# photon_at7020_2.net
KiCad netlist of a schematic drawn in EAGLE
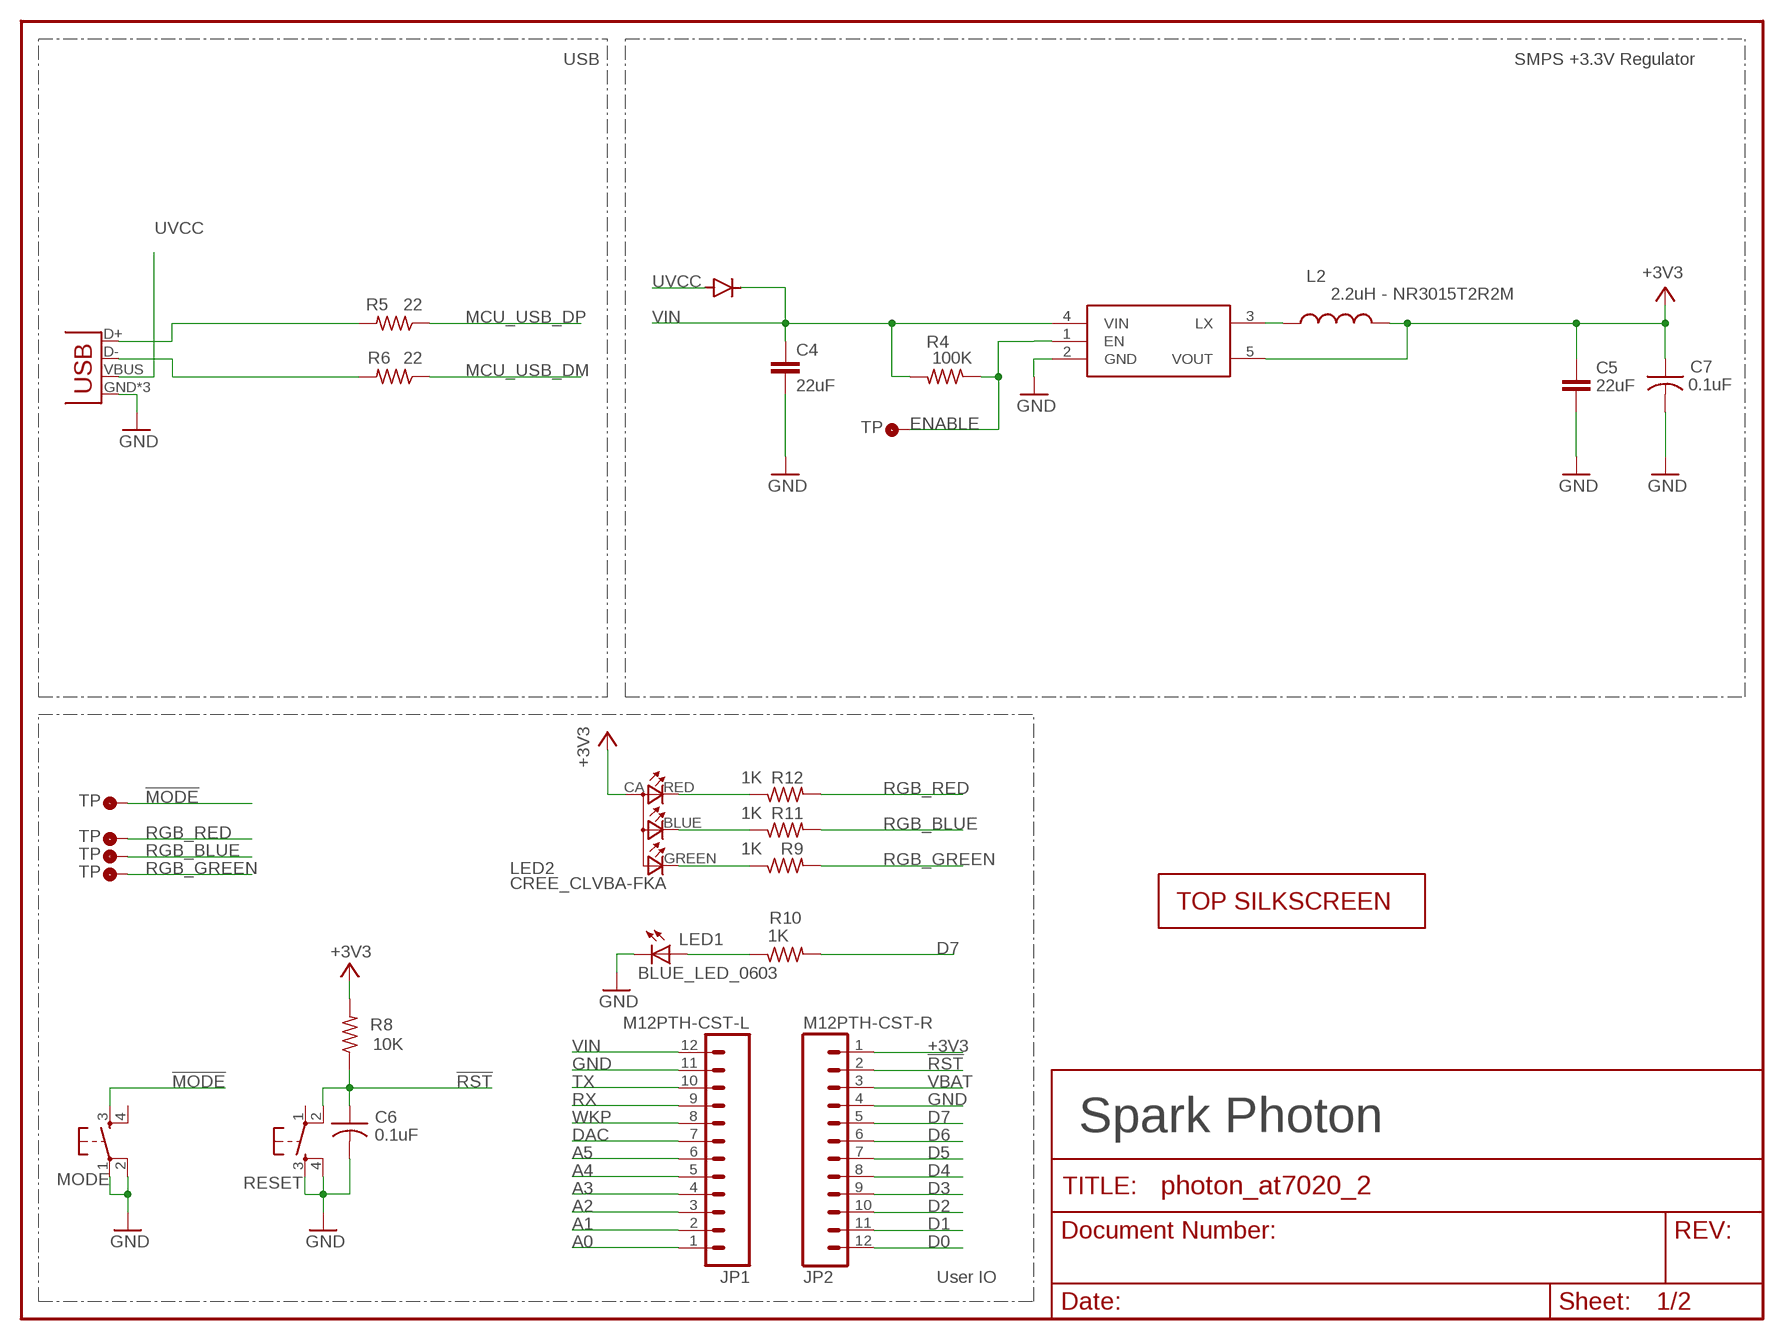
[diagram p0: schematic, sheet 1]
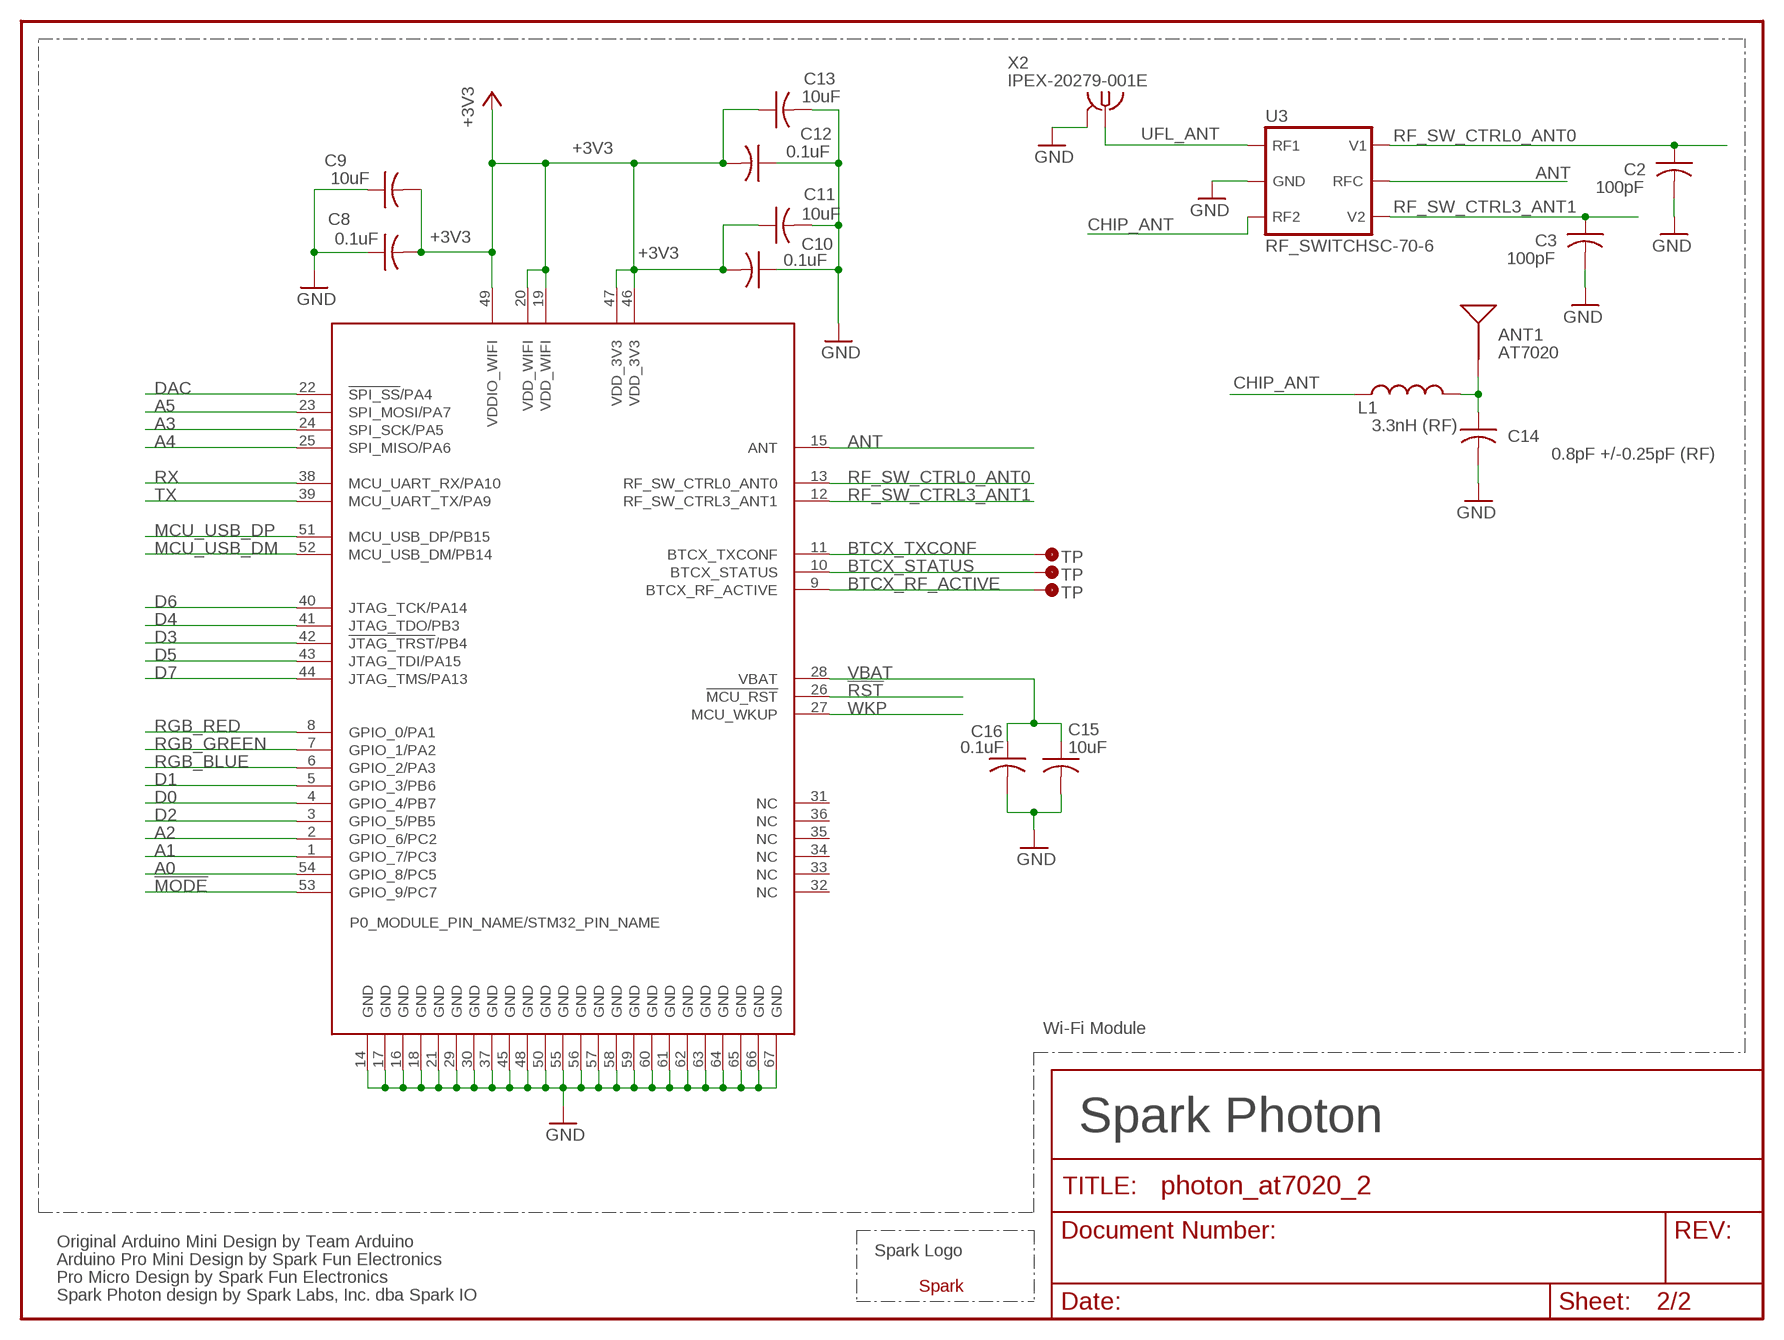
[diagram p1: schematic, sheet 2]

(export (version "E")
  (design (tool "Eeschema 10.0.6"))
  (components
    (comp (ref "ANT1")
      (value "AT7020")
      (footprint "eagle-import:AT7020")
      (libsource (lib "eagle-import") (part "AT7020"))
    )
    (comp (ref "C2")
      (value "100pF")
      (footprint "eagle-import:C0402_B")
      (libsource (lib "eagle-import") (part "C-US"))
    )
    (comp (ref "C3")
      (value "100pF")
      (footprint "eagle-import:C0402_B")
      (libsource (lib "eagle-import") (part "C-US"))
    )
    (comp (ref "C8")
      (value "0.1uF")
      (footprint "eagle-import:C0402_B")
      (libsource (lib "eagle-import") (part "C-US"))
    )
    (comp (ref "C9")
      (value "10uF")
      (footprint "eagle-import:C0402_B")
      (libsource (lib "eagle-import") (part "C-US"))
    )
    (comp (ref "C10")
      (value "0.1uF")
      (footprint "eagle-import:C0402_B")
      (libsource (lib "eagle-import") (part "C-US"))
    )
    (comp (ref "C11")
      (value "10uF")
      (footprint "eagle-import:C0402_B")
      (libsource (lib "eagle-import") (part "C-US"))
    )
    (comp (ref "C12")
      (value "0.1uF")
      (footprint "eagle-import:C0402_B")
      (libsource (lib "eagle-import") (part "C-US"))
    )
    (comp (ref "C13")
      (value "10uF")
      (footprint "eagle-import:C0402_B")
      (libsource (lib "eagle-import") (part "C-US"))
    )
    (comp (ref "C14")
      (value "0.8pF +/-0.25pF (RF)")
      (footprint "eagle-import:C0402_B")
      (libsource (lib "eagle-import") (part "C-US"))
    )
    (comp (ref "C15")
      (value "10uF")
      (footprint "eagle-import:C0402_B")
      (libsource (lib "eagle-import") (part "C-US"))
    )
    (comp (ref "C16")
      (value "0.1uF")
      (footprint "eagle-import:C0402_B")
      (libsource (lib "eagle-import") (part "C-US"))
    )
    (comp (ref "L1")
      (value "3.3nH (RF)")
      (footprint "eagle-import:L0402_B")
      (libsource (lib "eagle-import") (part "INDUCTOR"))
    )
    (comp (ref "U$2")
      (value "SPARK_LOGO2")
      (footprint "eagle-import:SPARK_LOGO2")
      (libsource (lib "eagle-import") (part "SPARK_LOGO2"))
    )
    (comp (ref "U$8")
      (value "TP1")
      (footprint "eagle-import:TP35_BOT")
      (libsource (lib "eagle-import") (part "TP1"))
    )
    (comp (ref "U$9")
      (value "TP1")
      (footprint "eagle-import:TP35_BOT")
      (libsource (lib "eagle-import") (part "TP1"))
    )
    (comp (ref "U$10")
      (value "TP1")
      (footprint "eagle-import:TP35_BOT")
      (libsource (lib "eagle-import") (part "TP1"))
    )
    (comp (ref "U1")
      (value "WM-N-BM-09")
      (footprint "eagle-import:WM-N-BM-09")
      (libsource (lib "eagle-import") (part "WM-N-BM-09"))
    )
    (comp (ref "U3")
      (value "RF_SWITCHSC-70-6")
      (footprint "eagle-import:SC70-6")
      (libsource (lib "eagle-import") (part "RF_SWITCHSC-70-6"))
    )
    (comp (ref "X2")
      (value "IPEX-20279-001E")
      (footprint "eagle-import:IPEX-20279-001E")
      (libsource (lib "eagle-import") (part "IPEX-20279-001E"))
    )
    (comp (ref "BLUE_LED_0603")
      (value "LED0603")
      (footprint "eagle-import:LED-0603")
      (libsource (lib "eagle-import") (part "LED0603"))
    )
    (comp (ref "C4")
      (value "22uF")
      (footprint "eagle-import:C0603")
      (libsource (lib "eagle-import") (part "C-EUC0603"))
    )
    (comp (ref "C5")
      (value "22uF")
      (footprint "eagle-import:C0603")
      (libsource (lib "eagle-import") (part "C-EUC0603"))
    )
    (comp (ref "C6")
      (value "0.1uF")
      (footprint "eagle-import:C0402_B")
      (libsource (lib "eagle-import") (part "C-US"))
    )
    (comp (ref "C7")
      (value "0.1uF")
      (footprint "eagle-import:C0402")
      (libsource (lib "eagle-import") (part "C-USC0402"))
    )
    (comp (ref "D1")
      (value "DIODE")
      (footprint "eagle-import:DIODE-DO-220AA(SMP)")
      (libsource (lib "eagle-import") (part "DIODE"))
    )
    (comp (ref "JP1")
      (value "M12PTH-CST-L")
      (footprint "eagle-import:1X12-CASTELLATED")
      (libsource (lib "eagle-import") (part "M12PTH-CST-L"))
    )
    (comp (ref "JP2")
      (value "M12PTH-CST-R")
      (footprint "eagle-import:1X12-CASTELLATED")
      (libsource (lib "eagle-import") (part "M12PTH-CST-R"))
    )
    (comp (ref "L2")
      (value "2.2uH - NR3015T2R2M")
      (footprint "eagle-import:INDUCTOR-NR3015")
      (libsource (lib "eagle-import") (part "INDUCTORB"))
    )
    (comp (ref "LED2")
      (value "CREE_CLVBA-FKA")
      (footprint "eagle-import:PLCC4-2MM-RGB")
      (libsource (lib "eagle-import") (part "RGB-LED-CLMVB-FKARGB"))
    )
    (comp (ref "MODE")
      (value "KMR211GLFS")
      (footprint "eagle-import:TACTILE_SWITCH_SMD")
      (libsource (lib "eagle-import") (part "TAC_SWITCHSMD"))
    )
    (comp (ref "R4")
      (value "100K")
      (footprint "eagle-import:R0402_B")
      (libsource (lib "eagle-import") (part "R-US_"))
    )
    (comp (ref "R5")
      (value "22")
      (footprint "eagle-import:R0402_B")
      (libsource (lib "eagle-import") (part "R-US_"))
    )
    (comp (ref "R6")
      (value "22")
      (footprint "eagle-import:R0402_B")
      (libsource (lib "eagle-import") (part "R-US_"))
    )
    (comp (ref "R8")
      (value "10K")
      (footprint "eagle-import:R0402_B")
      (libsource (lib "eagle-import") (part "R-US_"))
    )
    (comp (ref "R9")
      (value "1K")
      (footprint "eagle-import:R0402_B")
      (libsource (lib "eagle-import") (part "R-US_"))
    )
    (comp (ref "R10")
      (value "1K")
      (footprint "eagle-import:R0402_B")
      (libsource (lib "eagle-import") (part "R-US_"))
    )
    (comp (ref "R11")
      (value "1K")
      (footprint "eagle-import:R0402_B")
      (libsource (lib "eagle-import") (part "R-US_"))
    )
    (comp (ref "R12")
      (value "1K")
      (footprint "eagle-import:R0402_B")
      (libsource (lib "eagle-import") (part "R-US_"))
    )
    (comp (ref "RESET")
      (value "KMR211GLFS")
      (footprint "eagle-import:TACTILE_SWITCH_SMD")
      (libsource (lib "eagle-import") (part "TAC_SWITCHSMD"))
    )
    (comp (ref "U$1")
      (value "PHOTON-TOP-SS")
      (footprint "eagle-import:PHOTON-TOP-SS")
      (libsource (lib "eagle-import") (part "PHOTON-TOP-SS"))
    )
    (comp (ref "U$3")
      (value "TP1")
      (footprint "eagle-import:TP35_BOT")
      (libsource (lib "eagle-import") (part "TP1"))
    )
    (comp (ref "U$5")
      (value "TP1")
      (footprint "eagle-import:TP35_BOT")
      (libsource (lib "eagle-import") (part "TP1"))
    )
    (comp (ref "U$6")
      (value "TP1")
      (footprint "eagle-import:TP35_BOT")
      (libsource (lib "eagle-import") (part "TP1"))
    )
    (comp (ref "U$7")
      (value "TP1")
      (footprint "eagle-import:TP35_BOT")
      (libsource (lib "eagle-import") (part "TP1"))
    )
    (comp (ref "U$11")
      (value "R8008-33")
      (footprint "eagle-import:SOT23-5")
      (libsource (lib "eagle-import") (part "R8008-33"))
    )
    (comp (ref "U$12")
      (value "TP1")
      (footprint "eagle-import:TP35_BOT")
      (libsource (lib "eagle-import") (part "TP1"))
    )
    (comp (ref "X1")
      (value "USB-MICROB")
      (footprint "eagle-import:USB-MICROB-SLOT-HOLE")
      (libsource (lib "eagle-import") (part "USBUSB-MICROB-SLOT-HOLE"))
    )
  )
  (nets
    (net (code "1") (name "+3V3") (class "Default")
      (node (ref "C10") (pin "2") (pinfunction "2_2") (pintype "passive"))
      (node (ref "C11") (pin "1") (pinfunction "1_1") (pintype "passive"))
      (node (ref "C12") (pin "2") (pinfunction "2_2") (pintype "passive"))
      (node (ref "C13") (pin "1") (pinfunction "1_1") (pintype "passive"))
      (node (ref "C5") (pin "1") (pinfunction "1_1") (pintype "passive"))
      (node (ref "C7") (pin "1") (pinfunction "1_1") (pintype "passive"))
      (node (ref "C8") (pin "2") (pinfunction "2_2") (pintype "passive"))
      (node (ref "C9") (pin "2") (pinfunction "2_2") (pintype "passive"))
      (node (ref "JP2") (pin "1") (pinfunction "1_1") (pintype "passive"))
      (node (ref "L2") (pin "2") (pinfunction "2_2") (pintype "passive"))
      (node (ref "LED2") (pin "CA") (pinfunction "A2_CA") (pintype "passive"))
      (node (ref "R8") (pin "2") (pinfunction "2_2") (pintype "passive"))
      (node (ref "U$11") (pin "5") (pinfunction "VOUT_5") (pintype "bidirectional"))
      (node (ref "U1") (pin "19") (pinfunction "VDD_WIFI_19") (pintype "bidirectional"))
      (node (ref "U1") (pin "20") (pinfunction "VDD_WIFI_20") (pintype "bidirectional"))
      (node (ref "U1") (pin "46") (pinfunction "VDD_3V3_46") (pintype "bidirectional"))
      (node (ref "U1") (pin "47") (pinfunction "VDD_3V3_47") (pintype "bidirectional"))
      (node (ref "U1") (pin "49") (pinfunction "VDDIO_WIFI_49") (pintype "bidirectional"))
    )
    (net (code "2") (name "A0") (class "Default")
      (node (ref "JP1") (pin "1") (pinfunction "12_1") (pintype "passive"))
      (node (ref "U1") (pin "54") (pinfunction "GPIO_8/PC5_54") (pintype "bidirectional"))
    )
    (net (code "3") (name "A1") (class "Default")
      (node (ref "JP1") (pin "2") (pinfunction "11_2") (pintype "passive"))
      (node (ref "U1") (pin "1") (pinfunction "GPIO_7/PC3_1") (pintype "bidirectional"))
    )
    (net (code "4") (name "A2") (class "Default")
      (node (ref "JP1") (pin "3") (pinfunction "10_3") (pintype "passive"))
      (node (ref "U1") (pin "2") (pinfunction "GPIO_6/PC2_2") (pintype "bidirectional"))
    )
    (net (code "5") (name "A3") (class "Default")
      (node (ref "JP1") (pin "4") (pinfunction "9_4") (pintype "passive"))
      (node (ref "U1") (pin "24") (pinfunction "SPI_SCK/PA5_24") (pintype "bidirectional"))
    )
    (net (code "6") (name "A4") (class "Default")
      (node (ref "JP1") (pin "5") (pinfunction "8_5") (pintype "passive"))
      (node (ref "U1") (pin "25") (pinfunction "SPI_MISO/PA6_25") (pintype "bidirectional"))
    )
    (net (code "7") (name "A5") (class "Default")
      (node (ref "JP1") (pin "6") (pinfunction "7_6") (pintype "passive"))
      (node (ref "U1") (pin "23") (pinfunction "SPI_MOSI/PA7_23") (pintype "bidirectional"))
    )
    (net (code "8") (name "ANT") (class "Default")
      (node (ref "U1") (pin "15") (pinfunction "ANT_15") (pintype "bidirectional"))
      (node (ref "U3") (pin "5") (pinfunction "RFC_5") (pintype "input"))
    )
    (net (code "9") (name "BTCX_RF_ACTIVE") (class "Default")
      (node (ref "U$10") (pin "P$1") (pinfunction "TP_P$1") (pintype "bidirectional"))
      (node (ref "U1") (pin "9") (pinfunction "BTCX_RF_ACTIVE_9") (pintype "bidirectional"))
    )
    (net (code "10") (name "BTCX_STATUS") (class "Default")
      (node (ref "U$9") (pin "P$1") (pinfunction "TP_P$1") (pintype "bidirectional"))
      (node (ref "U1") (pin "10") (pinfunction "BTCX_STATUS_10") (pintype "bidirectional"))
    )
    (net (code "11") (name "BTCX_TXCONF") (class "Default")
      (node (ref "U$8") (pin "P$1") (pinfunction "TP_P$1") (pintype "bidirectional"))
      (node (ref "U1") (pin "11") (pinfunction "BTCX_TXCONF_11") (pintype "bidirectional"))
    )
    (net (code "12") (name "CHIP_ANT") (class "Default")
      (node (ref "L1") (pin "1") (pinfunction "1_1") (pintype "passive"))
      (node (ref "U3") (pin "3") (pinfunction "RF2_3") (pintype "output"))
    )
    (net (code "13") (name "D0") (class "Default")
      (node (ref "JP2") (pin "12") (pinfunction "12_12") (pintype "passive"))
      (node (ref "U1") (pin "4") (pinfunction "GPIO_4/PB7_4") (pintype "bidirectional"))
    )
    (net (code "14") (name "D1") (class "Default")
      (node (ref "JP2") (pin "11") (pinfunction "11_11") (pintype "passive"))
      (node (ref "U1") (pin "5") (pinfunction "GPIO_3/PB6_5") (pintype "bidirectional"))
    )
    (net (code "15") (name "D2") (class "Default")
      (node (ref "JP2") (pin "10") (pinfunction "10_10") (pintype "passive"))
      (node (ref "U1") (pin "3") (pinfunction "GPIO_5/PB5_3") (pintype "bidirectional"))
    )
    (net (code "16") (name "D3") (class "Default")
      (node (ref "JP2") (pin "9") (pinfunction "9_9") (pintype "passive"))
      (node (ref "U1") (pin "42") (pinfunction "~{JTAG_TRST}/PB4_42") (pintype "bidirectional"))
    )
    (net (code "17") (name "D4") (class "Default")
      (node (ref "JP2") (pin "8") (pinfunction "8_8") (pintype "passive"))
      (node (ref "U1") (pin "41") (pinfunction "JTAG_TDO/PB3_41") (pintype "bidirectional"))
    )
    (net (code "18") (name "D5") (class "Default")
      (node (ref "JP2") (pin "7") (pinfunction "7_7") (pintype "passive"))
      (node (ref "U1") (pin "43") (pinfunction "JTAG_TDI/PA15_43") (pintype "bidirectional"))
    )
    (net (code "19") (name "D6") (class "Default")
      (node (ref "JP2") (pin "6") (pinfunction "6_6") (pintype "passive"))
      (node (ref "U1") (pin "40") (pinfunction "JTAG_TCK/PA14_40") (pintype "bidirectional"))
    )
    (net (code "20") (name "D7") (class "Default")
      (node (ref "JP2") (pin "5") (pinfunction "5_5") (pintype "passive"))
      (node (ref "R10") (pin "2") (pinfunction "2_2") (pintype "passive"))
      (node (ref "U1") (pin "44") (pinfunction "JTAG_TMS/PA13_44") (pintype "bidirectional"))
    )
    (net (code "21") (name "DAC") (class "Default")
      (node (ref "JP1") (pin "7") (pinfunction "6_7") (pintype "passive"))
      (node (ref "U1") (pin "22") (pinfunction "~{SPI_SS}/PA4_22") (pintype "bidirectional"))
    )
    (net (code "22") (name "ENABLE") (class "Default")
      (node (ref "R4") (pin "1") (pinfunction "1_1") (pintype "passive"))
      (node (ref "U$11") (pin "1") (pinfunction "EN_1") (pintype "bidirectional"))
      (node (ref "U$12") (pin "P$1") (pinfunction "TP_P$1") (pintype "bidirectional"))
    )
    (net (code "23") (name "GND") (class "Default")
      (node (ref "BLUE_LED_0603") (pin "C") (pinfunction "C_C") (pintype "passive"))
      (node (ref "C10") (pin "1") (pinfunction "1_1") (pintype "passive"))
      (node (ref "C11") (pin "2") (pinfunction "2_2") (pintype "passive"))
      (node (ref "C12") (pin "1") (pinfunction "1_1") (pintype "passive"))
      (node (ref "C13") (pin "2") (pinfunction "2_2") (pintype "passive"))
      (node (ref "C14") (pin "2") (pinfunction "2_2") (pintype "passive"))
      (node (ref "C15") (pin "2") (pinfunction "2_2") (pintype "passive"))
      (node (ref "C16") (pin "2") (pinfunction "2_2") (pintype "passive"))
      (node (ref "C2") (pin "2") (pinfunction "2_2") (pintype "passive"))
      (node (ref "C3") (pin "2") (pinfunction "2_2") (pintype "passive"))
      (node (ref "C4") (pin "2") (pinfunction "2_2") (pintype "passive"))
      (node (ref "C5") (pin "2") (pinfunction "2_2") (pintype "passive"))
      (node (ref "C6") (pin "2") (pinfunction "2_2") (pintype "passive"))
      (node (ref "C7") (pin "2") (pinfunction "2_2") (pintype "passive"))
      (node (ref "C8") (pin "1") (pinfunction "1_1") (pintype "passive"))
      (node (ref "C9") (pin "1") (pinfunction "1_1") (pintype "passive"))
      (node (ref "JP1") (pin "11") (pinfunction "2_11") (pintype "passive"))
      (node (ref "JP2") (pin "4") (pinfunction "4_4") (pintype "passive"))
      (node (ref "MODE") (pin "1") (pinfunction "1_1") (pintype "passive"))
      (node (ref "MODE") (pin "2") (pinfunction "2_2") (pintype "passive"))
      (node (ref "RESET") (pin "3") (pinfunction "3_3") (pintype "passive"))
      (node (ref "RESET") (pin "4") (pinfunction "4_4") (pintype "passive"))
      (node (ref "U$11") (pin "2") (pinfunction "GND_2") (pintype "bidirectional"))
      (node (ref "U1") (pin "14") (pinfunction "GND_14") (pintype "bidirectional"))
      (node (ref "U1") (pin "16") (pinfunction "GND_16") (pintype "bidirectional"))
      (node (ref "U1") (pin "17") (pinfunction "GND_17") (pintype "bidirectional"))
      (node (ref "U1") (pin "18") (pinfunction "GND_18") (pintype "bidirectional"))
      (node (ref "U1") (pin "21") (pinfunction "GND_21") (pintype "bidirectional"))
      (node (ref "U1") (pin "29") (pinfunction "GND_29") (pintype "bidirectional"))
      (node (ref "U1") (pin "30") (pinfunction "GND_30") (pintype "bidirectional"))
      (node (ref "U1") (pin "37") (pinfunction "GND_37") (pintype "bidirectional"))
      (node (ref "U1") (pin "45") (pinfunction "GND_45") (pintype "bidirectional"))
      (node (ref "U1") (pin "48") (pinfunction "GND_48") (pintype "bidirectional"))
      (node (ref "U1") (pin "50") (pinfunction "GND_50") (pintype "bidirectional"))
      (node (ref "U1") (pin "55") (pinfunction "GND_55") (pintype "bidirectional"))
      (node (ref "U1") (pin "56") (pinfunction "GND_56") (pintype "bidirectional"))
      (node (ref "U1") (pin "57") (pinfunction "GND_57") (pintype "bidirectional"))
      (node (ref "U1") (pin "58") (pinfunction "GND_58") (pintype "bidirectional"))
      (node (ref "U1") (pin "59") (pinfunction "GND_59") (pintype "bidirectional"))
      (node (ref "U1") (pin "60") (pinfunction "GND_60") (pintype "bidirectional"))
      (node (ref "U1") (pin "61") (pinfunction "GND_61") (pintype "bidirectional"))
      (node (ref "U1") (pin "62") (pinfunction "GND_62") (pintype "bidirectional"))
      (node (ref "U1") (pin "63") (pinfunction "GND_63") (pintype "bidirectional"))
      (node (ref "U1") (pin "64") (pinfunction "GND_64") (pintype "bidirectional"))
      (node (ref "U1") (pin "65") (pinfunction "GND_65") (pintype "bidirectional"))
      (node (ref "U1") (pin "66") (pinfunction "GND_66") (pintype "bidirectional"))
      (node (ref "U1") (pin "67") (pinfunction "GND_67") (pintype "bidirectional"))
      (node (ref "U3") (pin "2") (pinfunction "GND_2") (pintype "power_in"))
      (node (ref "X1") (pin "GND") (pinfunction "GND_GND") (pintype "bidirectional"))
      (node (ref "X1") (pin "MT1") (pinfunction "GND_MT1") (pintype "bidirectional"))
      (node (ref "X1") (pin "MT2") (pinfunction "GND_MT2") (pintype "bidirectional"))
      (node (ref "X2") (pin "2@1") (pinfunction "GND_2@1") (pintype "passive"))
      (node (ref "X2") (pin "2@2") (pinfunction "GND_2@2") (pintype "passive"))
    )
    (net (code "24") (name "LED1") (class "Default")
      (node (ref "BLUE_LED_0603") (pin "A") (pinfunction "A_A") (pintype "passive"))
      (node (ref "R10") (pin "1") (pinfunction "1_1") (pintype "passive"))
    )
    (net (code "25") (name "MCU_USB_DM") (class "Default")
      (node (ref "R6") (pin "1") (pinfunction "1_1") (pintype "passive"))
      (node (ref "U1") (pin "52") (pinfunction "MCU_USB_DM/PB14_52") (pintype "bidirectional"))
    )
    (net (code "26") (name "MCU_USB_DP") (class "Default")
      (node (ref "R5") (pin "1") (pinfunction "1_1") (pintype "passive"))
      (node (ref "U1") (pin "51") (pinfunction "MCU_USB_DP/PB15_51") (pintype "bidirectional"))
    )
    (net (code "27") (name "Net-(ANT1-SIGNAL)") (class "Default")
      (node (ref "ANT1") (pin "1") (pinfunction "SIGNAL_1") (pintype "bidirectional"))
      (node (ref "C14") (pin "1") (pinfunction "1_1") (pintype "passive"))
      (node (ref "L1") (pin "2") (pinfunction "2_2") (pintype "passive"))
    )
    (net (code "28") (name "Net-(LED2-CBLUE)") (class "Default")
      (node (ref "LED2") (pin "BLUE") (pinfunction "CBLUE_BLUE") (pintype "passive"))
      (node (ref "R11") (pin "1") (pinfunction "1_1") (pintype "passive"))
    )
    (net (code "29") (name "Net-(LED2-CGREEN)") (class "Default")
      (node (ref "LED2") (pin "GREEN") (pinfunction "CGREEN_GREEN") (pintype "passive"))
      (node (ref "R9") (pin "1") (pinfunction "1_1") (pintype "passive"))
    )
    (net (code "30") (name "Net-(LED2-CRED)") (class "Default")
      (node (ref "LED2") (pin "RED") (pinfunction "CRED_RED") (pintype "passive"))
      (node (ref "R12") (pin "1") (pinfunction "1_1") (pintype "passive"))
    )
    (net (code "31") (name "Net-(R5-Pad2)") (class "Default")
      (node (ref "R5") (pin "2") (pinfunction "2_2") (pintype "passive"))
      (node (ref "X1") (pin "D+") (pinfunction "D+_D+") (pintype "bidirectional"))
    )
    (net (code "32") (name "Net-(R6-Pad2)") (class "Default")
      (node (ref "R6") (pin "2") (pinfunction "2_2") (pintype "passive"))
      (node (ref "X1") (pin "D-") (pinfunction "D-_D-") (pintype "bidirectional"))
    )
    (net (code "33") (name "Net-(U$11-LX)") (class "Default")
      (node (ref "L2") (pin "1") (pinfunction "1_1") (pintype "passive"))
      (node (ref "U$11") (pin "3") (pinfunction "LX_3") (pintype "bidirectional"))
    )
    (net (code "34") (name "RF_SW_CTRL0_ANT0") (class "Default")
      (node (ref "C2") (pin "1") (pinfunction "1_1") (pintype "passive"))
      (node (ref "U1") (pin "13") (pinfunction "RF_SW_CTRL0_ANT0_13") (pintype "bidirectional"))
      (node (ref "U3") (pin "6") (pinfunction "V1_6") (pintype "input"))
    )
    (net (code "35") (name "RF_SW_CTRL3_ANT1") (class "Default")
      (node (ref "C3") (pin "1") (pinfunction "1_1") (pintype "passive"))
      (node (ref "U1") (pin "12") (pinfunction "RF_SW_CTRL3_ANT1_12") (pintype "bidirectional"))
      (node (ref "U3") (pin "4") (pinfunction "V2_4") (pintype "input"))
    )
    (net (code "36") (name "RGB_BLUE") (class "Default")
      (node (ref "R11") (pin "2") (pinfunction "2_2") (pintype "passive"))
      (node (ref "U$6") (pin "P$1") (pinfunction "TP_P$1") (pintype "bidirectional"))
      (node (ref "U1") (pin "6") (pinfunction "GPIO_2/PA3_6") (pintype "bidirectional"))
    )
    (net (code "37") (name "RGB_GREEN") (class "Default")
      (node (ref "R9") (pin "2") (pinfunction "2_2") (pintype "passive"))
      (node (ref "U$7") (pin "P$1") (pinfunction "TP_P$1") (pintype "bidirectional"))
      (node (ref "U1") (pin "7") (pinfunction "GPIO_1/PA2_7") (pintype "bidirectional"))
    )
    (net (code "38") (name "RGB_RED") (class "Default")
      (node (ref "R12") (pin "2") (pinfunction "2_2") (pintype "passive"))
      (node (ref "U$5") (pin "P$1") (pinfunction "TP_P$1") (pintype "bidirectional"))
      (node (ref "U1") (pin "8") (pinfunction "GPIO_0/PA1_8") (pintype "bidirectional"))
    )
    (net (code "39") (name "RX") (class "Default")
      (node (ref "JP1") (pin "9") (pinfunction "4_9") (pintype "passive"))
      (node (ref "U1") (pin "38") (pinfunction "MCU_UART_RX/PA10_38") (pintype "bidirectional"))
    )
    (net (code "40") (name "TX") (class "Default")
      (node (ref "JP1") (pin "10") (pinfunction "3_10") (pintype "passive"))
      (node (ref "U1") (pin "39") (pinfunction "MCU_UART_TX/PA9_39") (pintype "bidirectional"))
    )
    (net (code "41") (name "UFL_ANT") (class "Default")
      (node (ref "U3") (pin "1") (pinfunction "RF1_1") (pintype "output"))
      (node (ref "X2") (pin "1") (pinfunction "1_1") (pintype "passive"))
    )
    (net (code "42") (name "UVCC") (class "Default")
      (node (ref "D1") (pin "ANODE") (pinfunction "ANODE_ANODE") (pintype "bidirectional"))
      (node (ref "X1") (pin "VBUS") (pinfunction "VBUS_VBUS") (pintype "bidirectional"))
    )
    (net (code "43") (name "VBAT") (class "Default")
      (node (ref "C15") (pin "1") (pinfunction "1_1") (pintype "passive"))
      (node (ref "C16") (pin "1") (pinfunction "1_1") (pintype "passive"))
      (node (ref "JP2") (pin "3") (pinfunction "3_3") (pintype "passive"))
      (node (ref "U1") (pin "28") (pinfunction "VBAT_28") (pintype "bidirectional"))
    )
    (net (code "44") (name "VIN") (class "Default")
      (node (ref "C4") (pin "1") (pinfunction "1_1") (pintype "passive"))
      (node (ref "D1") (pin "CATHODE") (pinfunction "CATHODE_CATHODE") (pintype "bidirectional"))
      (node (ref "JP1") (pin "12") (pinfunction "1_12") (pintype "passive"))
      (node (ref "R4") (pin "2") (pinfunction "2_2") (pintype "passive"))
      (node (ref "U$11") (pin "4") (pinfunction "VIN_4") (pintype "bidirectional"))
    )
    (net (code "45") (name "WKP") (class "Default")
      (node (ref "JP1") (pin "8") (pinfunction "5_8") (pintype "passive"))
      (node (ref "U1") (pin "27") (pinfunction "MCU_WKUP_27") (pintype "bidirectional"))
    )
    (net (code "46") (name "unconnected-(MODE-Pad4)") (class "Default")
      (node (ref "MODE") (pin "4") (pinfunction "4_4") (pintype "passive"))
    )
    (net (code "47") (name "unconnected-(RESET-Pad1)") (class "Default")
      (node (ref "RESET") (pin "1") (pinfunction "1_1") (pintype "passive"))
    )
    (net (code "48") (name "unconnected-(U1-NC-Pad31)") (class "Default")
      (node (ref "U1") (pin "31") (pinfunction "NC_31") (pintype "bidirectional"))
    )
    (net (code "49") (name "unconnected-(U1-NC-Pad32)") (class "Default")
      (node (ref "U1") (pin "32") (pinfunction "NC_32") (pintype "bidirectional"))
    )
    (net (code "50") (name "unconnected-(U1-NC-Pad33)") (class "Default")
      (node (ref "U1") (pin "33") (pinfunction "NC_33") (pintype "bidirectional"))
    )
    (net (code "51") (name "unconnected-(U1-NC-Pad34)") (class "Default")
      (node (ref "U1") (pin "34") (pinfunction "NC_34") (pintype "bidirectional"))
    )
    (net (code "52") (name "unconnected-(U1-NC-Pad35)") (class "Default")
      (node (ref "U1") (pin "35") (pinfunction "NC_35") (pintype "bidirectional"))
    )
    (net (code "53") (name "unconnected-(U1-NC-Pad36)") (class "Default")
      (node (ref "U1") (pin "36") (pinfunction "NC_36") (pintype "bidirectional"))
    )
    (net (code "54") (name "~{MODE}") (class "Default")
      (node (ref "MODE") (pin "3") (pinfunction "3_3") (pintype "passive"))
      (node (ref "U$3") (pin "P$1") (pinfunction "TP_P$1") (pintype "bidirectional"))
      (node (ref "U1") (pin "53") (pinfunction "GPIO_9/PC7_53") (pintype "bidirectional"))
    )
    (net (code "55") (name "~{RST}") (class "Default")
      (node (ref "C6") (pin "1") (pinfunction "1_1") (pintype "passive"))
      (node (ref "JP2") (pin "2") (pinfunction "2_2") (pintype "passive"))
      (node (ref "R8") (pin "1") (pinfunction "1_1") (pintype "passive"))
      (node (ref "RESET") (pin "2") (pinfunction "2_2") (pintype "passive"))
      (node (ref "U1") (pin "26") (pinfunction "~{MCU_RST}_26") (pintype "bidirectional"))
    )
  )
)
